# Ethernet.net
KiCad netlist of a schematic drawn in Altium Designer
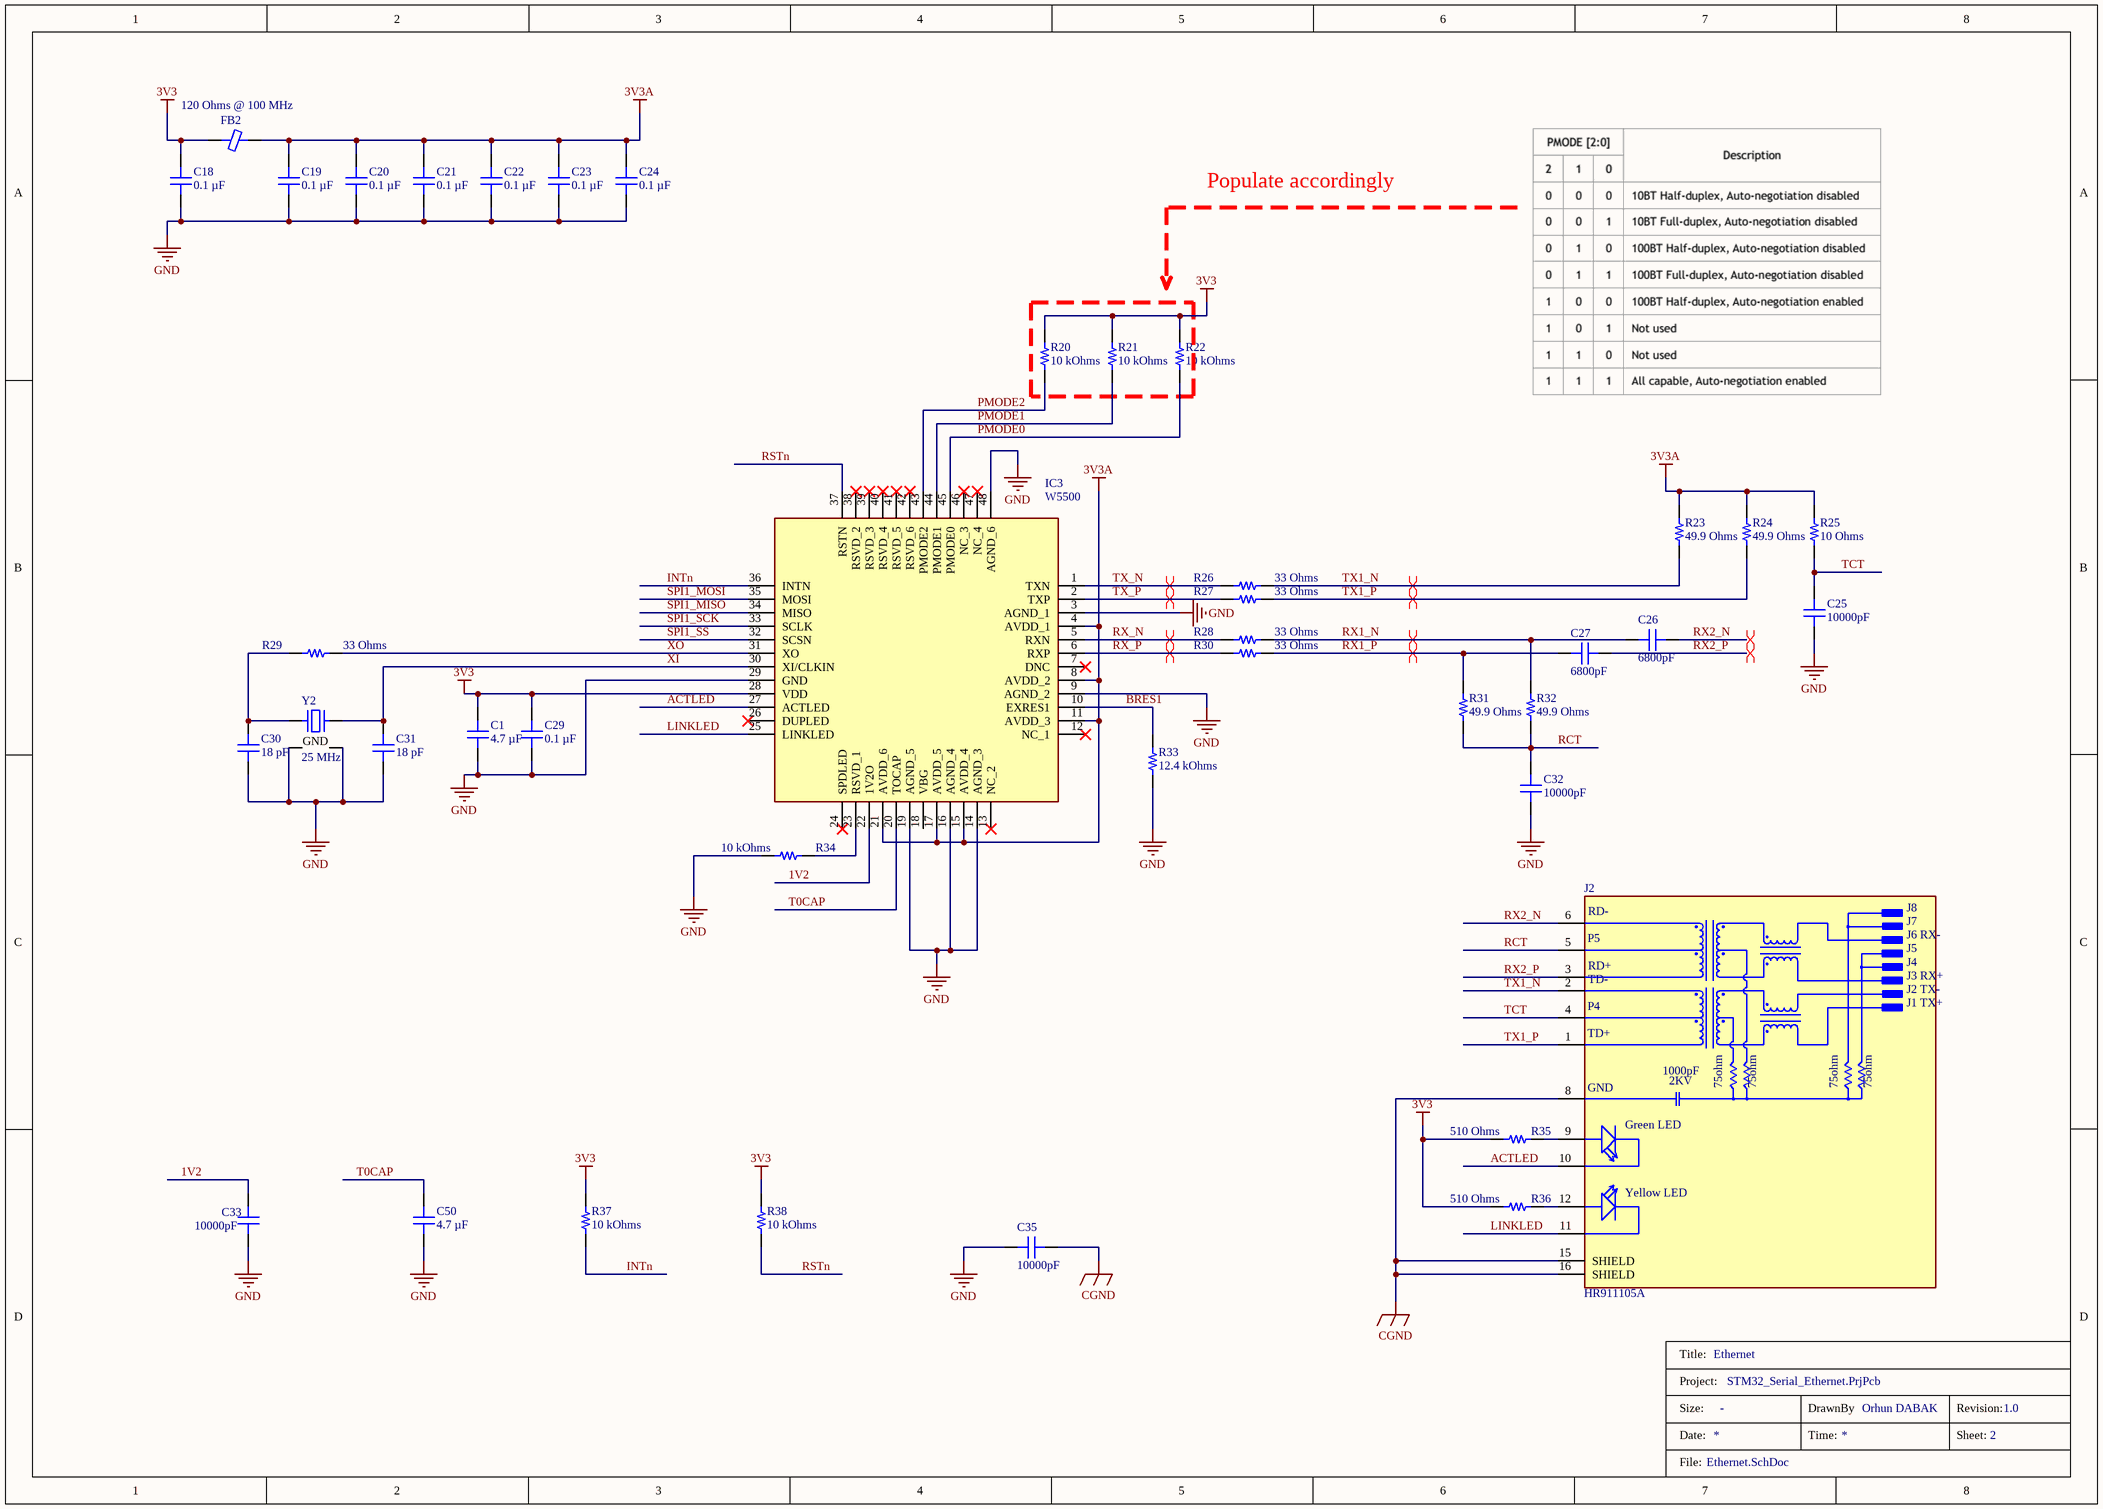
[diagram p0: Ethernet.SchDoc]

(export (version "E")
  (design (tool "Eeschema 10.0.6"))
  (components
    (comp (ref "C1")
      (value "4.7 µF")
      (footprint "CAP 0603_1608")
      (description "CAP CER 4.7UF 16V X6S 0603")
      (fields
        (field (name "PART NUMBER") "GRT188C81C475ME13D")
        (field (name "MANUFACTURER") "Murata Electronics")
      )
      (libsource (lib "Celestial Altium Library - altium_library") (part "Capacitor"))
    )
    (comp (ref "C18")
      (value "0.1 µF")
      (footprint "CAP 0603_1608")
      (description "CAP CER 0.1UF 16V X7R 0603")
      (fields (field (name "PART NUMBER") "CS0603KRX7R7BB104") (field (name "MANUFACTURER") "Yageo"))
      (libsource (lib "Celestial Altium Library - altium_library") (part "Capacitor"))
    )
    (comp (ref "C19")
      (value "0.1 µF")
      (footprint "CAP 0603_1608")
      (description "CAP CER 0.1UF 16V X7R 0603")
      (fields (field (name "PART NUMBER") "CS0603KRX7R7BB104") (field (name "MANUFACTURER") "Yageo"))
      (libsource (lib "Celestial Altium Library - altium_library") (part "Capacitor"))
    )
    (comp (ref "C20")
      (value "0.1 µF")
      (footprint "CAP 0603_1608")
      (description "CAP CER 0.1UF 16V X7R 0603")
      (fields (field (name "PART NUMBER") "CS0603KRX7R7BB104") (field (name "MANUFACTURER") "Yageo"))
      (libsource (lib "Celestial Altium Library - altium_library") (part "Capacitor"))
    )
    (comp (ref "C21")
      (value "0.1 µF")
      (footprint "CAP 0603_1608")
      (description "CAP CER 0.1UF 16V X7R 0603")
      (fields (field (name "PART NUMBER") "CS0603KRX7R7BB104") (field (name "MANUFACTURER") "Yageo"))
      (libsource (lib "Celestial Altium Library - altium_library") (part "Capacitor"))
    )
    (comp (ref "C22")
      (value "0.1 µF")
      (footprint "CAP 0603_1608")
      (description "CAP CER 0.1UF 16V X7R 0603")
      (fields (field (name "PART NUMBER") "CS0603KRX7R7BB104") (field (name "MANUFACTURER") "Yageo"))
      (libsource (lib "Celestial Altium Library - altium_library") (part "Capacitor"))
    )
    (comp (ref "C23")
      (value "0.1 µF")
      (footprint "CAP 0603_1608")
      (description "CAP CER 0.1UF 16V X7R 0603")
      (fields (field (name "PART NUMBER") "CS0603KRX7R7BB104") (field (name "MANUFACTURER") "Yageo"))
      (libsource (lib "Celestial Altium Library - altium_library") (part "Capacitor"))
    )
    (comp (ref "C24")
      (value "0.1 µF")
      (footprint "CAP 0603_1608")
      (description "CAP CER 0.1UF 16V X7R 0603")
      (fields (field (name "PART NUMBER") "CS0603KRX7R7BB104") (field (name "MANUFACTURER") "Yageo"))
      (libsource (lib "Celestial Altium Library - altium_library") (part "Capacitor"))
    )
    (comp (ref "C25")
      (value "10000pF")
      (footprint "CAP 0603_1608")
      (description "CAP CER 10000PF 16V X7R 0603")
      (fields (field (name "PART NUMBER") "0603YC103JAT2A") (field (name "MANUFACTURER") "AVX Corporation"))
      (libsource (lib "Celestial Altium Library - altium_library") (part "Capacitor"))
    )
    (comp (ref "C26")
      (value "6800pF")
      (footprint "CAP 0603_1608")
      (description "CAP CER 6800PF 50V X7R 0603")
      (fields (field (name "PART NUMBER") "06035C682KAT2A") (field (name "MANUFACTURER") "AVX Corporation"))
      (libsource (lib "Celestial Altium Library - altium_library") (part "Capacitor"))
    )
    (comp (ref "C27")
      (value "6800pF")
      (footprint "CAP 0603_1608")
      (description "CAP CER 6800PF 50V X7R 0603")
      (fields (field (name "PART NUMBER") "06035C682KAT2A") (field (name "MANUFACTURER") "AVX Corporation"))
      (libsource (lib "Celestial Altium Library - altium_library") (part "Capacitor"))
    )
    (comp (ref "C29")
      (value "0.1 µF")
      (footprint "CAP 0603_1608")
      (description "CAP CER 0.1UF 16V X7R 0603")
      (fields (field (name "PART NUMBER") "CS0603KRX7R7BB104") (field (name "MANUFACTURER") "Yageo"))
      (libsource (lib "Celestial Altium Library - altium_library") (part "Capacitor"))
    )
    (comp (ref "C30")
      (value "18 pF")
      (footprint "CAP 0603_1608")
      (description "CAP CER 18PF 50V C0G/NP0 0603")
      (fields
        (field (name "PART NUMBER") "VJ0603A180JXACW1BC")
        (field (name "MANUFACTURER") "Vishay Vitramon")
      )
      (libsource (lib "Celestial Altium Library - altium_library") (part "Capacitor"))
    )
    (comp (ref "C31")
      (value "18 pF")
      (footprint "CAP 0603_1608")
      (description "CAP CER 18PF 50V C0G/NP0 0603")
      (fields
        (field (name "PART NUMBER") "VJ0603A180JXACW1BC")
        (field (name "MANUFACTURER") "Vishay Vitramon")
      )
      (libsource (lib "Celestial Altium Library - altium_library") (part "Capacitor"))
    )
    (comp (ref "C32")
      (value "10000pF")
      (footprint "CAP 0603_1608")
      (description "CAP CER 10000PF 16V X7R 0603")
      (fields (field (name "PART NUMBER") "0603YC103JAT2A") (field (name "MANUFACTURER") "AVX Corporation"))
      (libsource (lib "Celestial Altium Library - altium_library") (part "Capacitor"))
    )
    (comp (ref "C33")
      (value "10000pF")
      (footprint "CAP 0603_1608")
      (description "CAP CER 10000PF 16V X7R 0603")
      (fields (field (name "PART NUMBER") "0603YC103JAT2A") (field (name "MANUFACTURER") "AVX Corporation"))
      (libsource (lib "Celestial Altium Library - altium_library") (part "Capacitor"))
    )
    (comp (ref "C35")
      (value "10000pF")
      (footprint "CAP 0603_1608")
      (description "CAP CER 10000PF 16V X7R 0603")
      (fields (field (name "PART NUMBER") "0603YC103JAT2A") (field (name "MANUFACTURER") "AVX Corporation"))
      (libsource (lib "Celestial Altium Library - altium_library") (part "Capacitor"))
    )
    (comp (ref "C50")
      (value "4.7 µF")
      (footprint "CAP 0603_1608")
      (description "CAP CER 4.7UF 16V X6S 0603")
      (fields
        (field (name "PART NUMBER") "GRT188C81C475ME13D")
        (field (name "MANUFACTURER") "Murata Electronics")
      )
      (libsource (lib "Celestial Altium Library - altium_library") (part "Capacitor"))
    )
    (comp (ref "FB2")
      (value "120 Ohms @ 100 MHz")
      (footprint "FER 0603_1608")
      (description "FERRITE BEAD 120 OHM 0603 1LN")
      (fields (field (name "PART NUMBER") "742792625") (field (name "MANUFACTURER") "Würth Elektronik"))
      (libsource (lib "Celestial Altium Library - altium_library") (part "Ferrite Chip"))
    )
    (comp (ref "IC3")
      (value "W5500")
      (footprint "SamacSys:QFP50P900X900X160-48N")
      (description "Integrated Circuit")
      (fields (field (name "MOUSER PART NUMBER") "950-W5500"))
      (libsource (lib "SamacSys") (part "W5500"))
    )
    (comp (ref "J2")
      (value "HR911105A")
      (footprint "HANRUN_HR911105A:HANRUN_HR911105A")
      (description "DIP RJ45 Connector;")
      (libsource (lib "HR911105A") (part "HR911105A"))
    )
    (comp (ref "R20")
      (value "10 kOhms")
      (footprint "RES 0603_1608")
      (description "RES SMD 10K OHM 5% 1/10W 0603")
      (fields (field (name "PART NUMBER") "CRCW060310K0JNEA") (field (name "MANUFACTURER") "Vishay Dale"))
      (libsource (lib "Celestial Altium Library - altium_library") (part "Resistor"))
    )
    (comp (ref "R21")
      (value "10 kOhms")
      (footprint "RES 0603_1608")
      (description "RES SMD 10K OHM 5% 1/10W 0603")
      (fields (field (name "PART NUMBER") "CRCW060310K0JNEA") (field (name "MANUFACTURER") "Vishay Dale"))
      (libsource (lib "Celestial Altium Library - altium_library") (part "Resistor"))
    )
    (comp (ref "R22")
      (value "10 kOhms")
      (footprint "RES 0603_1608")
      (description "RES SMD 10K OHM 5% 1/10W 0603")
      (fields (field (name "PART NUMBER") "CRCW060310K0JNEA") (field (name "MANUFACTURER") "Vishay Dale"))
      (libsource (lib "Celestial Altium Library - altium_library") (part "Resistor"))
    )
    (comp (ref "R23")
      (value "49.9 Ohms")
      (footprint "RES 0603_1608")
      (description "RES SMD 49.9 OHM 1% 1/10W 0603")
      (fields
        (field (name "PART NUMBER") "ERJ-3EKF49R9V")
        (field (name "MANUFACTURER") "Panasonic Electronic Components")
      )
      (libsource (lib "Celestial Altium Library - altium_library") (part "Resistor"))
    )
    (comp (ref "R24")
      (value "49.9 Ohms")
      (footprint "RES 0603_1608")
      (description "RES SMD 49.9 OHM 1% 1/10W 0603")
      (fields
        (field (name "PART NUMBER") "ERJ-3EKF49R9V")
        (field (name "MANUFACTURER") "Panasonic Electronic Components")
      )
      (libsource (lib "Celestial Altium Library - altium_library") (part "Resistor"))
    )
    (comp (ref "R25")
      (value "10 Ohms")
      (footprint "RES 0603_1608")
      (description "RES SMD 10 OHM 1% 1/10W 0603")
      (fields
        (field (name "PART NUMBER") "ERJ-3EKF10R0V")
        (field (name "MANUFACTURER") "Panasonic Electronic Components")
      )
      (libsource (lib "Celestial Altium Library - altium_library") (part "Resistor"))
    )
    (comp (ref "R26")
      (value "33 Ohms")
      (footprint "RES 0603_1608")
      (description "RES 33 OHM 5% 1/10W 0603")
      (fields
        (field (name "PART NUMBER") "RMCF0603JT33R0")
        (field (name "MANUFACTURER") "Stackpole Electronics Inc")
      )
      (libsource (lib "Celestial Altium Library - altium_library") (part "Resistor"))
    )
    (comp (ref "R27")
      (value "33 Ohms")
      (footprint "RES 0603_1608")
      (description "RES 33 OHM 5% 1/10W 0603")
      (fields
        (field (name "PART NUMBER") "RMCF0603JT33R0")
        (field (name "MANUFACTURER") "Stackpole Electronics Inc")
      )
      (libsource (lib "Celestial Altium Library - altium_library") (part "Resistor"))
    )
    (comp (ref "R28")
      (value "33 Ohms")
      (footprint "RES 0603_1608")
      (description "RES 33 OHM 5% 1/10W 0603")
      (fields
        (field (name "PART NUMBER") "RMCF0603JT33R0")
        (field (name "MANUFACTURER") "Stackpole Electronics Inc")
      )
      (libsource (lib "Celestial Altium Library - altium_library") (part "Resistor"))
    )
    (comp (ref "R29")
      (value "33 Ohms")
      (footprint "RES 0603_1608")
      (description "RES 33 OHM 5% 1/10W 0603")
      (fields
        (field (name "PART NUMBER") "RMCF0603JT33R0")
        (field (name "MANUFACTURER") "Stackpole Electronics Inc")
      )
      (libsource (lib "Celestial Altium Library - altium_library") (part "Resistor"))
    )
    (comp (ref "R30")
      (value "33 Ohms")
      (footprint "RES 0603_1608")
      (description "RES 33 OHM 5% 1/10W 0603")
      (fields
        (field (name "PART NUMBER") "RMCF0603JT33R0")
        (field (name "MANUFACTURER") "Stackpole Electronics Inc")
      )
      (libsource (lib "Celestial Altium Library - altium_library") (part "Resistor"))
    )
    (comp (ref "R31")
      (value "49.9 Ohms")
      (footprint "RES 0603_1608")
      (description "RES SMD 49.9 OHM 1% 1/10W 0603")
      (fields
        (field (name "PART NUMBER") "ERJ-3EKF49R9V")
        (field (name "MANUFACTURER") "Panasonic Electronic Components")
      )
      (libsource (lib "Celestial Altium Library - altium_library") (part "Resistor"))
    )
    (comp (ref "R32")
      (value "49.9 Ohms")
      (footprint "RES 0603_1608")
      (description "RES SMD 49.9 OHM 1% 1/10W 0603")
      (fields
        (field (name "PART NUMBER") "ERJ-3EKF49R9V")
        (field (name "MANUFACTURER") "Panasonic Electronic Components")
      )
      (libsource (lib "Celestial Altium Library - altium_library") (part "Resistor"))
    )
    (comp (ref "R33")
      (value "12.4 kOhms")
      (footprint "RES 0603_1608")
      (description "RES 12.4K OHM 1% 1/8W 0603")
      (fields
        (field (name "PART NUMBER") "RNCP0603FTD12K4")
        (field (name "MANUFACTURER") "Stackpole Electronics Inc")
      )
      (libsource (lib "Celestial Altium Library - altium_library") (part "Resistor"))
    )
    (comp (ref "R34")
      (value "10 kOhms")
      (footprint "RES 0603_1608")
      (description "RES SMD 10K OHM 5% 1/10W 0603")
      (fields (field (name "PART NUMBER") "CRCW060310K0JNEA") (field (name "MANUFACTURER") "Vishay Dale"))
      (libsource (lib "Celestial Altium Library - altium_library") (part "Resistor"))
    )
    (comp (ref "R35")
      (value "510 Ohms")
      (footprint "RES 0603_1608")
      (description "RES 510 OHM 5% 1/10W 0603")
      (fields
        (field (name "PART NUMBER") "RMCF0603JT510R")
        (field (name "MANUFACTURER") "Stackpole Electronics Inc")
      )
      (libsource (lib "Celestial Altium Library - altium_library") (part "Resistor"))
    )
    (comp (ref "R36")
      (value "510 Ohms")
      (footprint "RES 0603_1608")
      (description "RES 510 OHM 5% 1/10W 0603")
      (fields
        (field (name "PART NUMBER") "RMCF0603JT510R")
        (field (name "MANUFACTURER") "Stackpole Electronics Inc")
      )
      (libsource (lib "Celestial Altium Library - altium_library") (part "Resistor"))
    )
    (comp (ref "R37")
      (value "10 kOhms")
      (footprint "RES 0603_1608")
      (description "RES SMD 10K OHM 5% 1/10W 0603")
      (fields (field (name "PART NUMBER") "CRCW060310K0JNEA") (field (name "MANUFACTURER") "Vishay Dale"))
      (libsource (lib "Celestial Altium Library - altium_library") (part "Resistor"))
    )
    (comp (ref "R38")
      (value "10 kOhms")
      (footprint "RES 0603_1608")
      (description "RES SMD 10K OHM 5% 1/10W 0603")
      (fields (field (name "PART NUMBER") "CRCW060310K0JNEA") (field (name "MANUFACTURER") "Vishay Dale"))
      (libsource (lib "Celestial Altium Library - altium_library") (part "Resistor"))
    )
    (comp (ref "Y2")
      (value "25 MHz")
      (footprint "EPSON TSX-3225")
      (description "CRYSTAL 25.0000MHZ 18PF SMD")
      (fields (field (name "PART NUMBER") "TSX-3225 25.0000MF10P-C0") (field (name "MANUFACTURER") "EPSON"))
      (libsource (lib "Celestial Altium Library - altium_library") (part "Epson Crystal TSX-3225"))
    )
  )
  (nets
    (net (code "1") (name "/1V2") (class "Default")
      (node (ref "C33") (pin "2") (pinfunction "2_2") (pintype "passive"))
      (node (ref "IC3") (pin "22") (pinfunction "1V2O_22") (pintype "passive"))
    )
    (net (code "2") (name "/ACTLED") (class "Default")
      (node (ref "IC3") (pin "27") (pinfunction "ACTLED_27") (pintype "passive"))
      (node (ref "J2") (pin "10") (pinfunction "GC_10") (pintype "passive"))
    )
    (net (code "3") (name "/BRES1") (class "Default")
      (node (ref "IC3") (pin "10") (pinfunction "EXRES1_10") (pintype "passive"))
      (node (ref "R33") (pin "2") (pinfunction "2_2") (pintype "passive"))
    )
    (net (code "4") (name "/INTn") (class "Default")
      (node (ref "IC3") (pin "36") (pinfunction "INTN_36") (pintype "passive"))
      (node (ref "R37") (pin "2") (pinfunction "2_2") (pintype "passive"))
    )
    (net (code "5") (name "/LINKLED") (class "Default")
      (node (ref "IC3") (pin "25") (pinfunction "LINKLED_25") (pintype "passive"))
      (node (ref "J2") (pin "11") (pinfunction "YC_11") (pintype "passive"))
    )
    (net (code "6") (name "/PMODE0") (class "Default")
      (node (ref "IC3") (pin "45") (pinfunction "PMODE0_45") (pintype "passive"))
      (node (ref "R22") (pin "1") (pinfunction "1_1") (pintype "passive"))
    )
    (net (code "7") (name "/PMODE1") (class "Default")
      (node (ref "IC3") (pin "44") (pinfunction "PMODE1_44") (pintype "passive"))
      (node (ref "R21") (pin "1") (pinfunction "1_1") (pintype "passive"))
    )
    (net (code "8") (name "/PMODE2") (class "Default")
      (node (ref "IC3") (pin "43") (pinfunction "PMODE2_43") (pintype "passive"))
      (node (ref "R20") (pin "1") (pinfunction "1_1") (pintype "passive"))
    )
    (net (code "9") (name "/RCT") (class "Default")
      (node (ref "C32") (pin "2") (pinfunction "2_2") (pintype "passive"))
      (node (ref "J2") (pin "5") (pinfunction "P5_5") (pintype "passive"))
      (node (ref "R31") (pin "1") (pinfunction "1_1") (pintype "passive"))
      (node (ref "R32") (pin "1") (pinfunction "1_1") (pintype "passive"))
    )
    (net (code "10") (name "/RSTn") (class "Default")
      (node (ref "IC3") (pin "37") (pinfunction "RSTN_37") (pintype "passive"))
      (node (ref "R38") (pin "1") (pinfunction "1_1") (pintype "passive"))
    )
    (net (code "11") (name "/RX1_N") (class "Default")
      (node (ref "C26") (pin "1") (pinfunction "1_1") (pintype "passive"))
      (node (ref "R28") (pin "2") (pinfunction "2_2") (pintype "passive"))
      (node (ref "R32") (pin "2") (pinfunction "2_2") (pintype "passive"))
    )
    (net (code "12") (name "/RX1_P") (class "Default")
      (node (ref "C27") (pin "1") (pinfunction "1_1") (pintype "passive"))
      (node (ref "R30") (pin "2") (pinfunction "2_2") (pintype "passive"))
      (node (ref "R31") (pin "2") (pinfunction "2_2") (pintype "passive"))
    )
    (net (code "13") (name "/RX2_N") (class "Default")
      (node (ref "C26") (pin "2") (pinfunction "2_2") (pintype "passive"))
      (node (ref "J2") (pin "6") (pinfunction "RD-_6") (pintype "passive"))
    )
    (net (code "14") (name "/RX2_P") (class "Default")
      (node (ref "C27") (pin "2") (pinfunction "2_2") (pintype "passive"))
      (node (ref "J2") (pin "3") (pinfunction "RD+_3") (pintype "passive"))
    )
    (net (code "15") (name "/RX_N") (class "Default")
      (node (ref "IC3") (pin "5") (pinfunction "RXN_5") (pintype "passive"))
      (node (ref "R28") (pin "1") (pinfunction "1_1") (pintype "passive"))
    )
    (net (code "16") (name "/RX_P") (class "Default")
      (node (ref "IC3") (pin "6") (pinfunction "RXP_6") (pintype "passive"))
      (node (ref "R30") (pin "1") (pinfunction "1_1") (pintype "passive"))
    )
    (net (code "17") (name "/SPI1_MISO") (class "Default")
      (node (ref "IC3") (pin "34") (pinfunction "MISO_34") (pintype "passive"))
    )
    (net (code "18") (name "/SPI1_MOSI") (class "Default")
      (node (ref "IC3") (pin "35") (pinfunction "MOSI_35") (pintype "passive"))
    )
    (net (code "19") (name "/SPI1_SCK") (class "Default")
      (node (ref "IC3") (pin "33") (pinfunction "SCLK_33") (pintype "passive"))
    )
    (net (code "20") (name "/SPI1_SS") (class "Default")
      (node (ref "IC3") (pin "32") (pinfunction "SCSN_32") (pintype "passive"))
    )
    (net (code "21") (name "/T0CAP") (class "Default")
      (node (ref "C50") (pin "2") (pinfunction "2_2") (pintype "passive"))
      (node (ref "IC3") (pin "20") (pinfunction "TOCAP_20") (pintype "passive"))
    )
    (net (code "22") (name "/TCT") (class "Default")
      (node (ref "C25") (pin "2") (pinfunction "2_2") (pintype "passive"))
      (node (ref "J2") (pin "4") (pinfunction "P4_4") (pintype "passive"))
      (node (ref "R25") (pin "1") (pinfunction "1_1") (pintype "passive"))
    )
    (net (code "23") (name "/TX1_N") (class "Default")
      (node (ref "J2") (pin "2") (pinfunction "TD-_2") (pintype "passive"))
      (node (ref "R23") (pin "1") (pinfunction "1_1") (pintype "passive"))
      (node (ref "R26") (pin "2") (pinfunction "2_2") (pintype "passive"))
    )
    (net (code "24") (name "/TX1_P") (class "Default")
      (node (ref "J2") (pin "1") (pinfunction "TD+_1") (pintype "passive"))
      (node (ref "R24") (pin "1") (pinfunction "1_1") (pintype "passive"))
      (node (ref "R27") (pin "2") (pinfunction "2_2") (pintype "passive"))
    )
    (net (code "25") (name "/TX_N") (class "Default")
      (node (ref "IC3") (pin "1") (pinfunction "TXN_1") (pintype "passive"))
      (node (ref "R26") (pin "1") (pinfunction "1_1") (pintype "passive"))
    )
    (net (code "26") (name "/TX_P") (class "Default")
      (node (ref "IC3") (pin "2") (pinfunction "TXP_2") (pintype "passive"))
      (node (ref "R27") (pin "1") (pinfunction "1_1") (pintype "passive"))
    )
    (net (code "27") (name "/XI") (class "Default")
      (node (ref "C31") (pin "2") (pinfunction "2_2") (pintype "passive"))
      (node (ref "IC3") (pin "30") (pinfunction "XI/CLKIN_30") (pintype "passive"))
      (node (ref "Y2") (pin "3") (pinfunction "3_3") (pintype "passive"))
    )
    (net (code "28") (name "/XO") (class "Default")
      (node (ref "IC3") (pin "31") (pinfunction "XO_31") (pintype "passive"))
      (node (ref "R29") (pin "2") (pinfunction "2_2") (pintype "passive"))
    )
    (net (code "29") (name "3V3") (class "Default")
      (node (ref "C1") (pin "2") (pinfunction "2_2") (pintype "passive"))
      (node (ref "C18") (pin "1") (pinfunction "1_1") (pintype "passive"))
      (node (ref "C29") (pin "1") (pinfunction "1_1") (pintype "passive"))
      (node (ref "FB2") (pin "1") (pinfunction "1_1") (pintype "passive"))
      (node (ref "IC3") (pin "28") (pinfunction "VDD_28") (pintype "passive"))
      (node (ref "R20") (pin "2") (pinfunction "2_2") (pintype "passive"))
      (node (ref "R21") (pin "2") (pinfunction "2_2") (pintype "passive"))
      (node (ref "R22") (pin "2") (pinfunction "2_2") (pintype "passive"))
      (node (ref "R35") (pin "2") (pinfunction "2_2") (pintype "passive"))
      (node (ref "R36") (pin "2") (pinfunction "2_2") (pintype "passive"))
      (node (ref "R37") (pin "1") (pinfunction "1_1") (pintype "passive"))
      (node (ref "R38") (pin "2") (pinfunction "2_2") (pintype "passive"))
    )
    (net (code "30") (name "3V3A") (class "Default")
      (node (ref "C19") (pin "1") (pinfunction "1_1") (pintype "passive"))
      (node (ref "C20") (pin "1") (pinfunction "1_1") (pintype "passive"))
      (node (ref "C21") (pin "1") (pinfunction "1_1") (pintype "passive"))
      (node (ref "C22") (pin "1") (pinfunction "1_1") (pintype "passive"))
      (node (ref "C23") (pin "1") (pinfunction "1_1") (pintype "passive"))
      (node (ref "C24") (pin "1") (pinfunction "1_1") (pintype "passive"))
      (node (ref "FB2") (pin "2") (pinfunction "2_2") (pintype "passive"))
      (node (ref "IC3") (pin "11") (pinfunction "AVDD_3_11") (pintype "passive"))
      (node (ref "IC3") (pin "15") (pinfunction "AVDD_4_15") (pintype "passive"))
      (node (ref "IC3") (pin "17") (pinfunction "AVDD_5_17") (pintype "passive"))
      (node (ref "IC3") (pin "21") (pinfunction "AVDD_6_21") (pintype "passive"))
      (node (ref "IC3") (pin "4") (pinfunction "AVDD_1_4") (pintype "passive"))
      (node (ref "IC3") (pin "8") (pinfunction "AVDD_2_8") (pintype "passive"))
      (node (ref "R23") (pin "2") (pinfunction "2_2") (pintype "passive"))
      (node (ref "R24") (pin "2") (pinfunction "2_2") (pintype "passive"))
      (node (ref "R25") (pin "2") (pinfunction "2_2") (pintype "passive"))
    )
    (net (code "31") (name "CGND") (class "Default")
      (node (ref "C35") (pin "1") (pinfunction "1_1") (pintype "passive"))
      (node (ref "J2") (pin "15") (pinfunction "SHIELD_15") (pintype "passive"))
      (node (ref "J2") (pin "16") (pinfunction "SHIELD_16") (pintype "passive"))
      (node (ref "J2") (pin "8") (pinfunction "GND_8") (pintype "power_in"))
    )
    (net (code "32") (name "GND") (class "Default")
      (node (ref "C1") (pin "1") (pinfunction "1_1") (pintype "passive"))
      (node (ref "C18") (pin "2") (pinfunction "2_2") (pintype "passive"))
      (node (ref "C19") (pin "2") (pinfunction "2_2") (pintype "passive"))
      (node (ref "C20") (pin "2") (pinfunction "2_2") (pintype "passive"))
      (node (ref "C21") (pin "2") (pinfunction "2_2") (pintype "passive"))
      (node (ref "C22") (pin "2") (pinfunction "2_2") (pintype "passive"))
      (node (ref "C23") (pin "2") (pinfunction "2_2") (pintype "passive"))
      (node (ref "C24") (pin "2") (pinfunction "2_2") (pintype "passive"))
      (node (ref "C25") (pin "1") (pinfunction "1_1") (pintype "passive"))
      (node (ref "C29") (pin "2") (pinfunction "2_2") (pintype "passive"))
      (node (ref "C30") (pin "1") (pinfunction "1_1") (pintype "passive"))
      (node (ref "C31") (pin "1") (pinfunction "1_1") (pintype "passive"))
      (node (ref "C32") (pin "1") (pinfunction "1_1") (pintype "passive"))
      (node (ref "C33") (pin "1") (pinfunction "1_1") (pintype "passive"))
      (node (ref "C35") (pin "2") (pinfunction "2_2") (pintype "passive"))
      (node (ref "C50") (pin "1") (pinfunction "1_1") (pintype "passive"))
      (node (ref "IC3") (pin "14") (pinfunction "AGND_3_14") (pintype "passive"))
      (node (ref "IC3") (pin "16") (pinfunction "AGND_4_16") (pintype "passive"))
      (node (ref "IC3") (pin "19") (pinfunction "AGND_5_19") (pintype "passive"))
      (node (ref "IC3") (pin "29") (pinfunction "GND_29") (pintype "passive"))
      (node (ref "IC3") (pin "3") (pinfunction "AGND_1_3") (pintype "passive"))
      (node (ref "IC3") (pin "48") (pinfunction "AGND_6_48") (pintype "passive"))
      (node (ref "IC3") (pin "9") (pinfunction "AGND_2_9") (pintype "passive"))
      (node (ref "R33") (pin "1") (pinfunction "1_1") (pintype "passive"))
      (node (ref "R34") (pin "2") (pinfunction "2_2") (pintype "passive"))
      (node (ref "Y2") (pin "2") (pinfunction "GND_2") (pintype "passive"))
      (node (ref "Y2") (pin "4") (pinfunction "GND_4") (pintype "passive"))
    )
    (net (code "33") (name "Net-(C30-Pad2)") (class "Default")
      (node (ref "C30") (pin "2") (pinfunction "2_2") (pintype "passive"))
      (node (ref "R29") (pin "1") (pinfunction "1_1") (pintype "passive"))
      (node (ref "Y2") (pin "1") (pinfunction "1_1") (pintype "passive"))
    )
    (net (code "34") (name "Net-(IC3-RSVD_1)") (class "Default")
      (node (ref "IC3") (pin "23") (pinfunction "RSVD_1_23") (pintype "passive"))
      (node (ref "R34") (pin "1") (pinfunction "1_1") (pintype "passive"))
    )
    (net (code "35") (name "Net-(J2-GA)") (class "Default")
      (node (ref "J2") (pin "9") (pinfunction "GA_9") (pintype "passive"))
      (node (ref "R35") (pin "1") (pinfunction "1_1") (pintype "passive"))
    )
    (net (code "36") (name "Net-(J2-YA)") (class "Default")
      (node (ref "J2") (pin "12") (pinfunction "YA_12") (pintype "passive"))
      (node (ref "R36") (pin "1") (pinfunction "1_1") (pintype "passive"))
    )
    (net (code "37") (name "unconnected-(IC3-DNC-Pad7)") (class "Default")
      (node (ref "IC3") (pin "7") (pinfunction "DNC_7") (pintype "passive+no_connect"))
    )
    (net (code "38") (name "unconnected-(IC3-DUPLED-Pad26)") (class "Default")
      (node (ref "IC3") (pin "26") (pinfunction "DUPLED_26") (pintype "passive+no_connect"))
    )
    (net (code "39") (name "unconnected-(IC3-NC_1-Pad12)") (class "Default")
      (node (ref "IC3") (pin "12") (pinfunction "NC_1_12") (pintype "passive+no_connect"))
    )
    (net (code "40") (name "unconnected-(IC3-NC_2-Pad13)") (class "Default")
      (node (ref "IC3") (pin "13") (pinfunction "NC_2_13") (pintype "passive+no_connect"))
    )
    (net (code "41") (name "unconnected-(IC3-NC_3-Pad46)") (class "Default")
      (node (ref "IC3") (pin "46") (pinfunction "NC_3_46") (pintype "passive+no_connect"))
    )
    (net (code "42") (name "unconnected-(IC3-NC_4-Pad47)") (class "Default")
      (node (ref "IC3") (pin "47") (pinfunction "NC_4_47") (pintype "passive+no_connect"))
    )
    (net (code "43") (name "unconnected-(IC3-RSVD_2-Pad38)") (class "Default")
      (node (ref "IC3") (pin "38") (pinfunction "RSVD_2_38") (pintype "passive+no_connect"))
    )
    (net (code "44") (name "unconnected-(IC3-RSVD_3-Pad39)") (class "Default")
      (node (ref "IC3") (pin "39") (pinfunction "RSVD_3_39") (pintype "passive+no_connect"))
    )
    (net (code "45") (name "unconnected-(IC3-RSVD_4-Pad40)") (class "Default")
      (node (ref "IC3") (pin "40") (pinfunction "RSVD_4_40") (pintype "passive+no_connect"))
    )
    (net (code "46") (name "unconnected-(IC3-RSVD_5-Pad41)") (class "Default")
      (node (ref "IC3") (pin "41") (pinfunction "RSVD_5_41") (pintype "passive+no_connect"))
    )
    (net (code "47") (name "unconnected-(IC3-RSVD_6-Pad42)") (class "Default")
      (node (ref "IC3") (pin "42") (pinfunction "RSVD_6_42") (pintype "passive+no_connect"))
    )
    (net (code "48") (name "unconnected-(IC3-SPDLED-Pad24)") (class "Default")
      (node (ref "IC3") (pin "24") (pinfunction "SPDLED_24") (pintype "passive+no_connect"))
    )
    (net (code "49") (name "unconnected-(IC3-VBG-Pad18)") (class "Default")
      (node (ref "IC3") (pin "18") (pinfunction "VBG_18") (pintype "passive"))
    )
  )
)
